# Microcontroller.net
KiCad netlist of a schematic drawn in Altium Designer
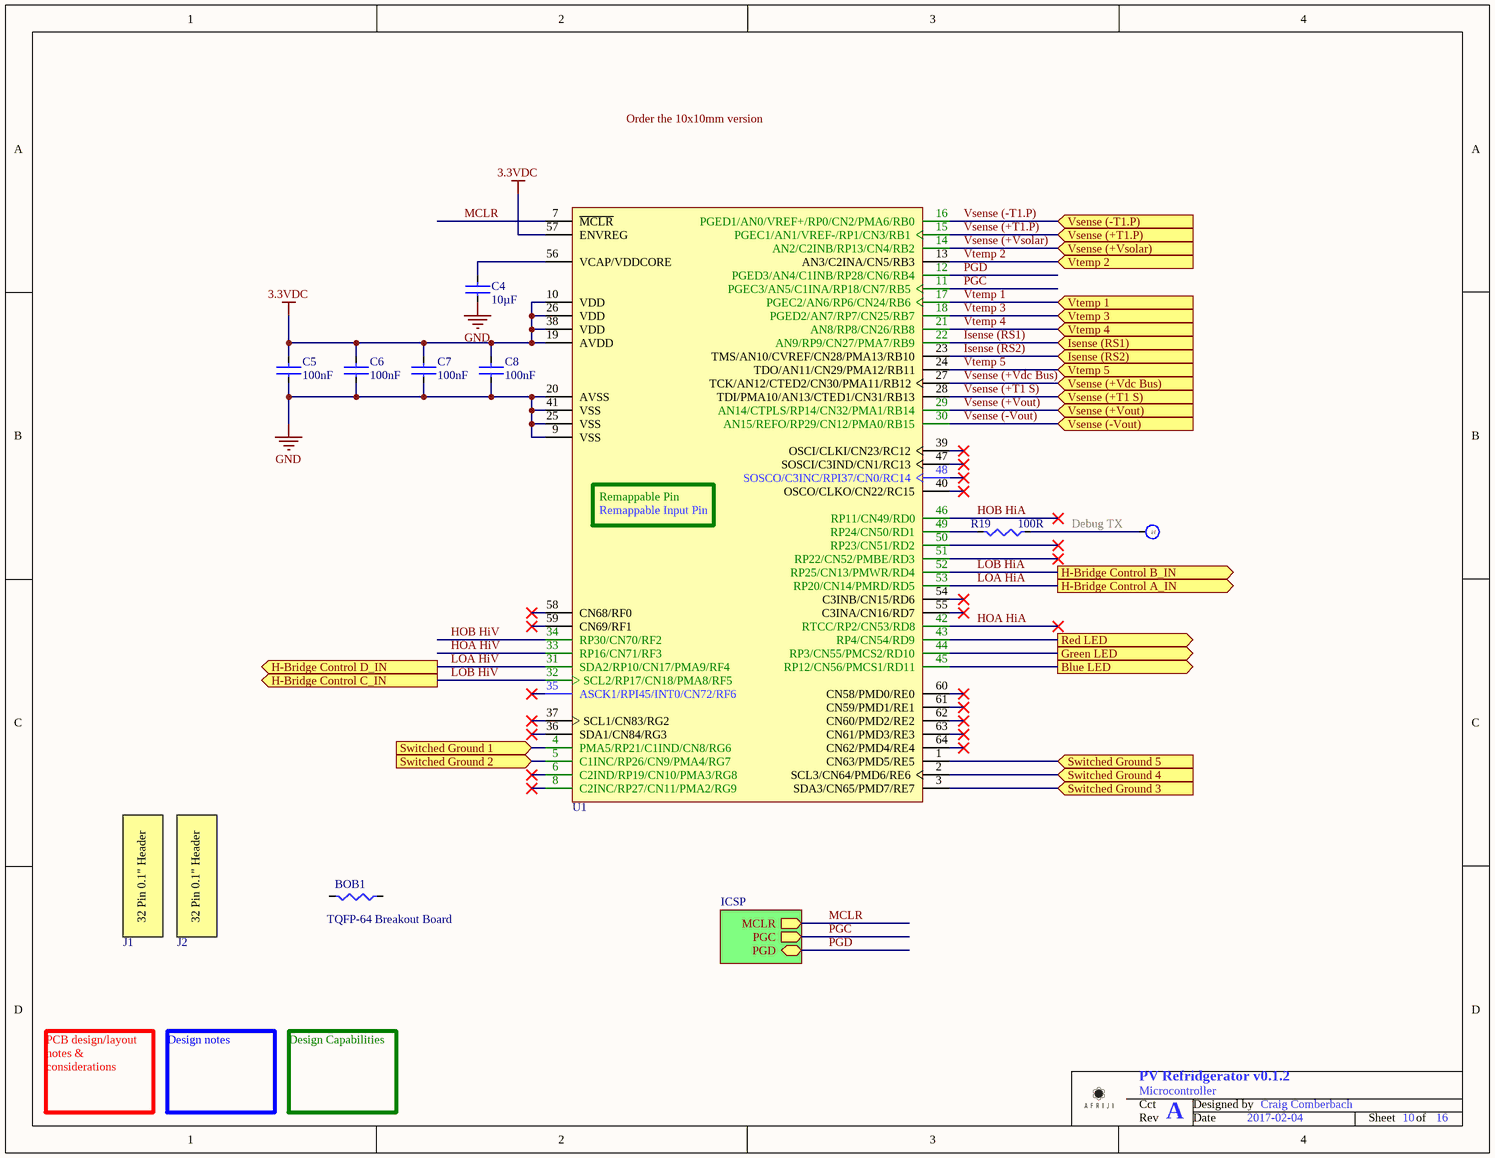
[diagram p0: Microcontroller.SchDoc]

(export (version "E")
  (design (tool "Eeschema 10.0.6"))
  (components
    (comp (ref "BOB1")
      (value "TQFP-64 Breakout Board")
      (description "1/8W")
      (fields
        (field (name "MANUFACTURER") "Chip Quik Inc.")
        (field (name "MANUFACTURER PART NUMBER") "PA0096")
      )
      (libsource (lib "Personal Library") (part "1k 1210 1%"))
    )
    (comp (ref "C4")
      (value "10uF 0805 10V")
      (footprint "C0805 - Ceramic")
      (fields
        (field (name "MANUFACTURER") "Kemet")
        (field (name "MANUFACTURER PART NUMBER") "C0805C106K8PACTU")
        (field (name "TOLERANCE") "±10%")
        (field (name "CAPACITANCE") "10µF")
      )
      (libsource (lib "Personal Library") (part "10uF 0805 10V"))
    )
    (comp (ref "C5")
      (value "100nF 0603 50V")
      (footprint "C0603 - Ceramic")
      (fields
        (field (name "MANUFACTURER") "Samsung Electro-Mechanics America, Inc")
        (field (name "MANUFACTURER PART NUMBER") "CL10B104KB8SFNC")
        (field (name "TOLERANCE") "±10%")
        (field (name "CAPACITANCE") "100nF")
      )
      (libsource (lib "Personal Library") (part "100nF 0603 50V"))
    )
    (comp (ref "C6")
      (value "100nF 0603 50V")
      (footprint "C0603 - Ceramic")
      (fields
        (field (name "MANUFACTURER") "Samsung Electro-Mechanics America, Inc")
        (field (name "MANUFACTURER PART NUMBER") "CL10B104KB8SFNC")
        (field (name "TOLERANCE") "±10%")
        (field (name "CAPACITANCE") "100nF")
      )
      (libsource (lib "Personal Library") (part "100nF 0603 50V"))
    )
    (comp (ref "C7")
      (value "100nF 0603 50V")
      (footprint "C0603 - Ceramic")
      (fields
        (field (name "MANUFACTURER") "Samsung Electro-Mechanics America, Inc")
        (field (name "MANUFACTURER PART NUMBER") "CL10B104KB8SFNC")
        (field (name "TOLERANCE") "±10%")
        (field (name "CAPACITANCE") "100nF")
      )
      (libsource (lib "Personal Library") (part "100nF 0603 50V"))
    )
    (comp (ref "C8")
      (value "100nF 0603 50V")
      (footprint "C0603 - Ceramic")
      (fields
        (field (name "MANUFACTURER") "Samsung Electro-Mechanics America, Inc")
        (field (name "MANUFACTURER PART NUMBER") "CL10B104KB8SFNC")
        (field (name "TOLERANCE") "±10%")
        (field (name "CAPACITANCE") "100nF")
      )
      (libsource (lib "Personal Library") (part "100nF 0603 50V"))
    )
    (comp (ref "J1")
      (value "32-Pin 0.1\" Header")
      (fields
        (field (name "MANUFACTURER") "Wurth Electronics Inc")
        (field (name "MANUFACTURER PART NUMBER") "61303211821")
      )
      (libsource (lib "Local Library") (part "32-Pin 0.1{dblquote} Header"))
    )
    (comp (ref "J2")
      (value "32-Pin 0.1\" Header")
      (fields
        (field (name "MANUFACTURER") "Wurth Electronics Inc")
        (field (name "MANUFACTURER PART NUMBER") "61303211821")
      )
      (libsource (lib "Local Library") (part "32-Pin 0.1{dblquote} Header"))
    )
    (comp (ref "R19")
      (value "100R 0603 1%")
      (footprint "R0603")
      (description "1/8W")
      (fields
        (field (name "MANUFACTURER") "Yageo")
        (field (name "MANUFACTURER PART NUMBER") "RC0603FR-07100RL")
        (field (name "RESISTANCE (OHMS)") "100R")
      )
      (libsource (lib "Personal Library") (part "100R 0603 1%"))
    )
    (comp (ref "TP3")
      (value "Test Clip")
      (footprint "SMT Test Clip")
      (fields
        (field (name "MANUFACTURER") "TE Connectivity AMP Connectors")
        (field (name "MANUFACTURER PART NUMBER") "RCU-0C")
      )
      (libsource (lib "Integrated Component Library") (part "Test Clip"))
    )
    (comp (ref "U1")
      (value "PIC24FJ256GA106 Microprocessor")
      (footprint "TQFP-64 0.5mm Breakout Board")
      (fields
        (field (name "MANUFACTURER") "Microchip Technology")
        (field (name "MANUFACTURER PART NUMBER") "PIC24FJ256GA106-I/PT")
      )
      (libsource (lib "Integrated Component Library") (part "PIC24FJ256GA106 Microprocessor"))
    )
  )
  (nets
    (net (code "1") (name "/Blue LED") (class "Default")
      (node (ref "U1") (pin "45") (pinfunction "RP12/CN56/PMCS1/RD11_45") (pintype "passive"))
    )
    (net (code "2") (name "/Debug TX") (class "Default")
      (node (ref "R19") (pin "2") (pinfunction "2_2") (pintype "passive"))
      (node (ref "TP3") (pin "1") (pinfunction "1_1") (pintype "passive"))
    )
    (net (code "3") (name "/Green LED") (class "Default")
      (node (ref "U1") (pin "44") (pinfunction "RP3/CN55/PMCS2/RD10_44") (pintype "passive"))
    )
    (net (code "4") (name "/HOA HiA") (class "Default")
      (node (ref "U1") (pin "42") (pinfunction "RTCC/RP2/CN53/RD8_42") (pintype "passive+no_connect"))
    )
    (net (code "5") (name "/HOA HiV") (class "Default")
      (node (ref "U1") (pin "33") (pinfunction "RP16/CN71/RF3_33") (pintype "passive"))
    )
    (net (code "6") (name "/HOB HiA") (class "Default")
      (node (ref "U1") (pin "46") (pinfunction "RP11/CN49/RD0_46") (pintype "passive+no_connect"))
    )
    (net (code "7") (name "/HOB HiV") (class "Default")
      (node (ref "U1") (pin "34") (pinfunction "RP30/CN70/RF2_34") (pintype "passive"))
    )
    (net (code "8") (name "/Isense (RS1)") (class "Default")
      (node (ref "U1") (pin "22") (pinfunction "AN9/RP9/CN27/PMA7/RB9_22") (pintype "passive"))
    )
    (net (code "9") (name "/Isense (RS2)") (class "Default")
      (node (ref "U1") (pin "23") (pinfunction "TMS/AN10/CVREF/CN28/PMA13/RB10_23") (pintype "passive"))
    )
    (net (code "10") (name "/LOA HiA") (class "Default")
      (node (ref "U1") (pin "53") (pinfunction "RP20/CN14/PMRD/RD5_53") (pintype "passive"))
    )
    (net (code "11") (name "/LOA HiV") (class "Default")
      (node (ref "U1") (pin "31") (pinfunction "SDA2/RP10/CN17/PMA9/RF4_31") (pintype "passive"))
    )
    (net (code "12") (name "/LOB HiA") (class "Default")
      (node (ref "U1") (pin "52") (pinfunction "RP25/CN13/PMWR/RD4_52") (pintype "passive"))
    )
    (net (code "13") (name "/LOB HiV") (class "Default")
      (node (ref "U1") (pin "32") (pinfunction "SCL2/RP17/CN18/PMA8/RF5_32") (pintype "passive"))
    )
    (net (code "14") (name "/MCLR") (class "Default")
      (node (ref "U1") (pin "7") (pinfunction "~{MCLR}_7") (pintype "passive"))
    )
    (net (code "16") (name "/PGC") (class "Default")
      (node (ref "U1") (pin "11") (pinfunction "PGEC3/AN5/C1INA/RP18/CN7/RB5_11") (pintype "passive"))
    )
    (net (code "17") (name "/PGD") (class "Default")
      (node (ref "U1") (pin "12") (pinfunction "PGED3/AN4/C1INB/RP28/CN6/RB4_12") (pintype "passive"))
    )
    (net (code "18") (name "/Red LED") (class "Default")
      (node (ref "U1") (pin "43") (pinfunction "RP4/CN54/RD9_43") (pintype "passive"))
    )
    (net (code "19") (name "/Switched Ground 1") (class "Default")
      (node (ref "U1") (pin "4") (pinfunction "PMA5/RP21/C1IND/CN8/RG6_4") (pintype "passive"))
    )
    (net (code "20") (name "/Switched Ground 2") (class "Default")
      (node (ref "U1") (pin "5") (pinfunction "C1INC/RP26/CN9/PMA4/RG7_5") (pintype "passive"))
    )
    (net (code "21") (name "/Switched Ground 3") (class "Default")
      (node (ref "U1") (pin "3") (pinfunction "SDA3/CN65/PMD7/RE7_3") (pintype "passive"))
    )
    (net (code "22") (name "/Switched Ground 4") (class "Default")
      (node (ref "U1") (pin "2") (pinfunction "SCL3/CN64/PMD6/RE6_2") (pintype "passive"))
    )
    (net (code "23") (name "/Switched Ground 5") (class "Default")
      (node (ref "U1") (pin "1") (pinfunction "CN63/PMD5/RE5_1") (pintype "passive"))
    )
    (net (code "24") (name "/Vsense (+T1 S)") (class "Default")
      (node (ref "U1") (pin "28") (pinfunction "TDI/PMA10/AN13/CTED1/CN31/RB13_28") (pintype "passive"))
    )
    (net (code "25") (name "/Vsense (+T1.P)") (class "Default")
      (node (ref "U1") (pin "15") (pinfunction "PGEC1/AN1/VREF-/RP1/CN3/RB1_15") (pintype "passive"))
    )
    (net (code "26") (name "/Vsense (+Vdc Bus)") (class "Default")
      (node (ref "U1") (pin "27") (pinfunction "TCK/AN12/CTED2/CN30/PMA11/RB12_27") (pintype "passive"))
    )
    (net (code "27") (name "/Vsense (+Vout)") (class "Default")
      (node (ref "U1") (pin "29") (pinfunction "AN14/CTPLS/RP14/CN32/PMA1/RB14_29") (pintype "passive"))
    )
    (net (code "28") (name "/Vsense (+Vsolar)") (class "Default")
      (node (ref "U1") (pin "14") (pinfunction "AN2/C2INB/RP13/CN4/RB2_14") (pintype "passive"))
    )
    (net (code "29") (name "/Vsense (-T1.P)") (class "Default")
      (node (ref "U1") (pin "16") (pinfunction "PGED1/AN0/VREF+/RP0/CN2/PMA6/RB0_16") (pintype "passive"))
    )
    (net (code "30") (name "/Vsense (-Vout)") (class "Default")
      (node (ref "U1") (pin "30") (pinfunction "AN15/REFO/RP29/CN12/PMA0/RB15_30") (pintype "passive"))
    )
    (net (code "31") (name "/Vtemp 1") (class "Default")
      (node (ref "U1") (pin "17") (pinfunction "PGEC2/AN6/RP6/CN24/RB6_17") (pintype "passive"))
    )
    (net (code "32") (name "/Vtemp 2") (class "Default")
      (node (ref "U1") (pin "13") (pinfunction "AN3/C2INA/CN5/RB3_13") (pintype "passive"))
    )
    (net (code "33") (name "/Vtemp 3") (class "Default")
      (node (ref "U1") (pin "18") (pinfunction "PGED2/AN7/RP7/CN25/RB7_18") (pintype "passive"))
    )
    (net (code "34") (name "/Vtemp 4") (class "Default")
      (node (ref "U1") (pin "21") (pinfunction "AN8/RP8/CN26/RB8_21") (pintype "passive"))
    )
    (net (code "35") (name "/Vtemp 5") (class "Default")
      (node (ref "U1") (pin "24") (pinfunction "TDO/AN11/CN29/PMA12/RB11_24") (pintype "passive"))
    )
    (net (code "36") (name "3.3VDC") (class "Default")
      (node (ref "C5") (pin "1") (pinfunction "1_1") (pintype "passive"))
      (node (ref "C6") (pin "1") (pinfunction "1_1") (pintype "passive"))
      (node (ref "C7") (pin "1") (pinfunction "1_1") (pintype "passive"))
      (node (ref "C8") (pin "1") (pinfunction "1_1") (pintype "passive"))
      (node (ref "U1") (pin "10") (pinfunction "VDD_10") (pintype "passive"))
      (node (ref "U1") (pin "19") (pinfunction "AVDD_19") (pintype "passive"))
      (node (ref "U1") (pin "26") (pinfunction "VDD_26") (pintype "passive"))
      (node (ref "U1") (pin "38") (pinfunction "VDD_38") (pintype "passive"))
      (node (ref "U1") (pin "57") (pinfunction "ENVREG_57") (pintype "passive"))
    )
    (net (code "37") (name "GND") (class "Default")
      (node (ref "C4") (pin "2") (pinfunction "2_2") (pintype "passive"))
      (node (ref "C5") (pin "2") (pinfunction "2_2") (pintype "passive"))
      (node (ref "C6") (pin "2") (pinfunction "2_2") (pintype "passive"))
      (node (ref "C7") (pin "2") (pinfunction "2_2") (pintype "passive"))
      (node (ref "C8") (pin "2") (pinfunction "2_2") (pintype "passive"))
      (node (ref "U1") (pin "20") (pinfunction "AVSS_20") (pintype "passive"))
      (node (ref "U1") (pin "25") (pinfunction "VSS_25") (pintype "passive"))
      (node (ref "U1") (pin "41") (pinfunction "VSS_41") (pintype "passive"))
      (node (ref "U1") (pin "9") (pinfunction "VSS_9") (pintype "passive"))
    )
    (net (code "38") (name "Net-(U1-RP24{slash}CN50{slash}RD1)") (class "Default")
      (node (ref "R19") (pin "1") (pinfunction "1_1") (pintype "passive"))
      (node (ref "U1") (pin "49") (pinfunction "RP24/CN50/RD1_49") (pintype "passive"))
    )
    (net (code "39") (name "Net-(U1-VCAP{slash}VDDCORE)") (class "Default")
      (node (ref "C4") (pin "1") (pinfunction "1_1") (pintype "passive"))
      (node (ref "U1") (pin "56") (pinfunction "VCAP/VDDCORE_56") (pintype "passive"))
    )
    (net (code "40") (name "unconnected-(BOB1-Pad1)") (class "Default")
      (node (ref "BOB1") (pin "1") (pinfunction "1_1") (pintype "passive"))
    )
    (net (code "41") (name "unconnected-(BOB1-Pad2)") (class "Default")
      (node (ref "BOB1") (pin "2") (pinfunction "2_2") (pintype "passive"))
    )
    (net (code "42") (name "unconnected-(U1-ASCK1{slash}RPI45{slash}INT0{slash}CN72{slash}RF6-Pad35)") (class "Default")
      (node (ref "U1") (pin "35") (pinfunction "ASCK1/RPI45/INT0/CN72/RF6_35") (pintype "passive+no_connect"))
    )
    (net (code "43") (name "unconnected-(U1-C2INC{slash}RP27{slash}CN11{slash}PMA2{slash}RG9-Pad8)") (class "Default")
      (node (ref "U1") (pin "8") (pinfunction "C2INC/RP27/CN11/PMA2/RG9_8") (pintype "passive+no_connect"))
    )
    (net (code "44") (name "unconnected-(U1-C2IND{slash}RP19{slash}CN10{slash}PMA3{slash}RG8-Pad6)") (class "Default")
      (node (ref "U1") (pin "6") (pinfunction "C2IND/RP19/CN10/PMA3/RG8_6") (pintype "passive+no_connect"))
    )
    (net (code "45") (name "unconnected-(U1-C3INA{slash}CN16{slash}RD7-Pad55)") (class "Default")
      (node (ref "U1") (pin "55") (pinfunction "C3INA/CN16/RD7_55") (pintype "passive+no_connect"))
    )
    (net (code "46") (name "unconnected-(U1-C3INB{slash}CN15{slash}RD6-Pad54)") (class "Default")
      (node (ref "U1") (pin "54") (pinfunction "C3INB/CN15/RD6_54") (pintype "passive+no_connect"))
    )
    (net (code "47") (name "unconnected-(U1-CN58{slash}PMD0{slash}RE0-Pad60)") (class "Default")
      (node (ref "U1") (pin "60") (pinfunction "CN58/PMD0/RE0_60") (pintype "passive+no_connect"))
    )
    (net (code "48") (name "unconnected-(U1-CN59{slash}PMD1{slash}RE1-Pad61)") (class "Default")
      (node (ref "U1") (pin "61") (pinfunction "CN59/PMD1/RE1_61") (pintype "passive+no_connect"))
    )
    (net (code "49") (name "unconnected-(U1-CN60{slash}PMD2{slash}RE2-Pad62)") (class "Default")
      (node (ref "U1") (pin "62") (pinfunction "CN60/PMD2/RE2_62") (pintype "passive+no_connect"))
    )
    (net (code "50") (name "unconnected-(U1-CN61{slash}PMD3{slash}RE3-Pad63)") (class "Default")
      (node (ref "U1") (pin "63") (pinfunction "CN61/PMD3/RE3_63") (pintype "passive+no_connect"))
    )
    (net (code "51") (name "unconnected-(U1-CN62{slash}PMD4{slash}RE4-Pad64)") (class "Default")
      (node (ref "U1") (pin "64") (pinfunction "CN62/PMD4/RE4_64") (pintype "passive+no_connect"))
    )
    (net (code "52") (name "unconnected-(U1-CN68{slash}RF0-Pad58)") (class "Default")
      (node (ref "U1") (pin "58") (pinfunction "CN68/RF0_58") (pintype "passive+no_connect"))
    )
    (net (code "53") (name "unconnected-(U1-CN69{slash}RF1-Pad59)") (class "Default")
      (node (ref "U1") (pin "59") (pinfunction "CN69/RF1_59") (pintype "passive+no_connect"))
    )
    (net (code "54") (name "unconnected-(U1-OSCI{slash}CLKI{slash}CN23{slash}RC12-Pad39)") (class "Default")
      (node (ref "U1") (pin "39") (pinfunction "OSCI/CLKI/CN23/RC12_39") (pintype "passive+no_connect"))
    )
    (net (code "55") (name "unconnected-(U1-OSCO{slash}CLKO{slash}CN22{slash}RC15-Pad40)") (class "Default")
      (node (ref "U1") (pin "40") (pinfunction "OSCO/CLKO/CN22/RC15_40") (pintype "passive+no_connect"))
    )
    (net (code "56") (name "unconnected-(U1-RP22{slash}CN52{slash}PMBE{slash}RD3-Pad51)") (class "Default")
      (node (ref "U1") (pin "51") (pinfunction "RP22/CN52/PMBE/RD3_51") (pintype "passive+no_connect"))
    )
    (net (code "57") (name "unconnected-(U1-RP23{slash}CN51{slash}RD2-Pad50)") (class "Default")
      (node (ref "U1") (pin "50") (pinfunction "RP23/CN51/RD2_50") (pintype "passive+no_connect"))
    )
    (net (code "58") (name "unconnected-(U1-SCL1{slash}CN83{slash}RG2-Pad37)") (class "Default")
      (node (ref "U1") (pin "37") (pinfunction "SCL1/CN83/RG2_37") (pintype "passive+no_connect"))
    )
    (net (code "59") (name "unconnected-(U1-SDA1{slash}CN84{slash}RG3-Pad36)") (class "Default")
      (node (ref "U1") (pin "36") (pinfunction "SDA1/CN84/RG3_36") (pintype "passive+no_connect"))
    )
    (net (code "60") (name "unconnected-(U1-SOSCI{slash}C3IND{slash}CN1{slash}RC13-Pad47)") (class "Default")
      (node (ref "U1") (pin "47") (pinfunction "SOSCI/C3IND/CN1/RC13_47") (pintype "passive+no_connect"))
    )
    (net (code "61") (name "unconnected-(U1-SOSCO{slash}C3INC{slash}RPI37{slash}CN0{slash}RC14-Pad48)") (class "Default")
      (node (ref "U1") (pin "48") (pinfunction "SOSCO/C3INC/RPI37/CN0/RC14_48") (pintype "passive+no_connect"))
    )
  )
)
